# sensores.net
KiCad netlist of a schematic drawn in EAGLE
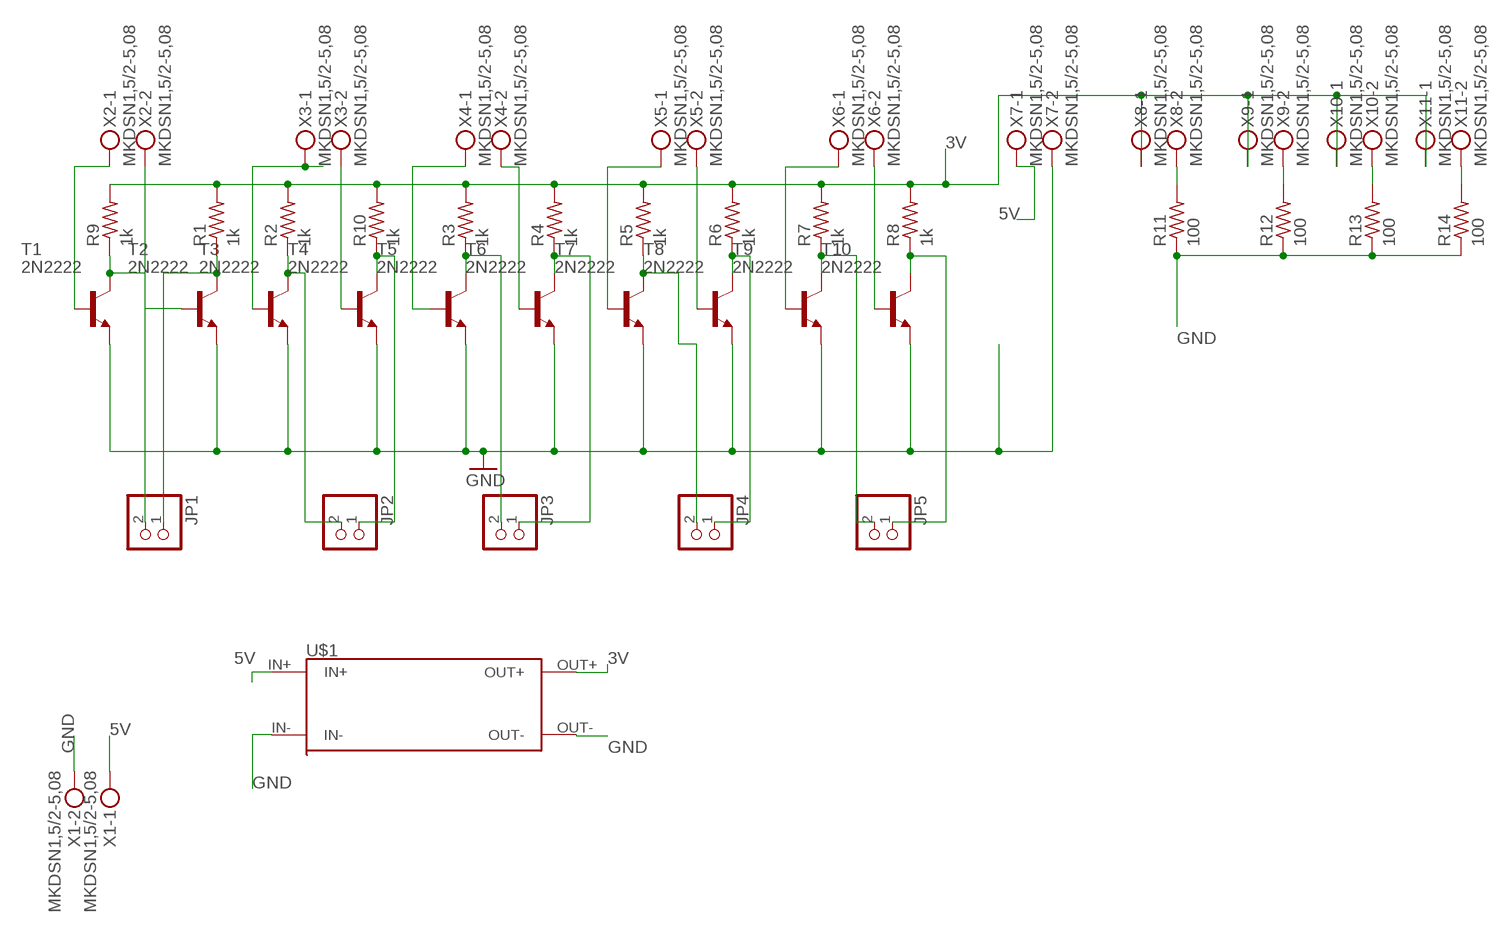
[diagram p0: schematic, sheet 1]

(export (version "E")
  (design (tool "Eeschema 10.0.6"))
  (components
    (comp (ref "JP1")
      (value "PINHD-1X2")
      (footprint "eagle-import:1X02")
      (libsource (lib "eagle-import") (part "PINHD-1X2"))
    )
    (comp (ref "JP2")
      (value "PINHD-1X2")
      (footprint "eagle-import:1X02")
      (libsource (lib "eagle-import") (part "PINHD-1X2"))
    )
    (comp (ref "JP3")
      (value "PINHD-1X2")
      (footprint "eagle-import:1X02")
      (libsource (lib "eagle-import") (part "PINHD-1X2"))
    )
    (comp (ref "JP4")
      (value "PINHD-1X2")
      (footprint "eagle-import:1X02")
      (libsource (lib "eagle-import") (part "PINHD-1X2"))
    )
    (comp (ref "JP5")
      (value "PINHD-1X2")
      (footprint "eagle-import:1X02")
      (libsource (lib "eagle-import") (part "PINHD-1X2"))
    )
    (comp (ref "R1")
      (value "1k")
      (footprint "eagle-import:0207_10")
      (libsource (lib "eagle-import") (part "R-US_0207/10"))
    )
    (comp (ref "R2")
      (value "1k")
      (footprint "eagle-import:0207_10")
      (libsource (lib "eagle-import") (part "R-US_0207/10"))
    )
    (comp (ref "R3")
      (value "1k")
      (footprint "eagle-import:0207_10")
      (libsource (lib "eagle-import") (part "R-US_0207/10"))
    )
    (comp (ref "R4")
      (value "1k")
      (footprint "eagle-import:0207_10")
      (libsource (lib "eagle-import") (part "R-US_0207/10"))
    )
    (comp (ref "R5")
      (value "1k")
      (footprint "eagle-import:0207_10")
      (libsource (lib "eagle-import") (part "R-US_0207/10"))
    )
    (comp (ref "R6")
      (value "1k")
      (footprint "eagle-import:0207_10")
      (libsource (lib "eagle-import") (part "R-US_0207/10"))
    )
    (comp (ref "R7")
      (value "1k")
      (footprint "eagle-import:0207_10")
      (libsource (lib "eagle-import") (part "R-US_0207/10"))
    )
    (comp (ref "R8")
      (value "1k")
      (footprint "eagle-import:0207_10")
      (libsource (lib "eagle-import") (part "R-US_0207/10"))
    )
    (comp (ref "R9")
      (value "1k")
      (footprint "eagle-import:0207_10")
      (libsource (lib "eagle-import") (part "R-US_0207/10"))
    )
    (comp (ref "R10")
      (value "1k")
      (footprint "eagle-import:0207_10")
      (libsource (lib "eagle-import") (part "R-US_0207/10"))
    )
    (comp (ref "R11")
      (value "100")
      (footprint "eagle-import:0207_10")
      (libsource (lib "eagle-import") (part "R-US_0207/10"))
    )
    (comp (ref "R12")
      (value "100")
      (footprint "eagle-import:0207_10")
      (libsource (lib "eagle-import") (part "R-US_0207/10"))
    )
    (comp (ref "R13")
      (value "100")
      (footprint "eagle-import:0207_10")
      (libsource (lib "eagle-import") (part "R-US_0207/10"))
    )
    (comp (ref "R14")
      (value "100")
      (footprint "eagle-import:0207_10")
      (libsource (lib "eagle-import") (part "R-US_0207/10"))
    )
    (comp (ref "T1")
      (value "2N2222")
      (footprint "eagle-import:2N2222")
      (libsource (lib "eagle-import") (part "2N2222"))
    )
    (comp (ref "T2")
      (value "2N2222")
      (footprint "eagle-import:2N2222")
      (libsource (lib "eagle-import") (part "2N2222"))
    )
    (comp (ref "T3")
      (value "2N2222")
      (footprint "eagle-import:2N2222")
      (libsource (lib "eagle-import") (part "2N2222"))
    )
    (comp (ref "T4")
      (value "2N2222")
      (footprint "eagle-import:2N2222")
      (libsource (lib "eagle-import") (part "2N2222"))
    )
    (comp (ref "T5")
      (value "2N2222")
      (footprint "eagle-import:2N2222")
      (libsource (lib "eagle-import") (part "2N2222"))
    )
    (comp (ref "T6")
      (value "2N2222")
      (footprint "eagle-import:2N2222")
      (libsource (lib "eagle-import") (part "2N2222"))
    )
    (comp (ref "T7")
      (value "2N2222")
      (footprint "eagle-import:2N2222")
      (libsource (lib "eagle-import") (part "2N2222"))
    )
    (comp (ref "T8")
      (value "2N2222")
      (footprint "eagle-import:2N2222")
      (libsource (lib "eagle-import") (part "2N2222"))
    )
    (comp (ref "T9")
      (value "2N2222")
      (footprint "eagle-import:2N2222")
      (libsource (lib "eagle-import") (part "2N2222"))
    )
    (comp (ref "T10")
      (value "2N2222")
      (footprint "eagle-import:2N2222")
      (libsource (lib "eagle-import") (part "2N2222"))
    )
    (comp (ref "U$1")
      (value "LM2596")
      (footprint "eagle-import:LM2596")
      (libsource (lib "eagle-import") (part "LM2596"))
    )
    (comp (ref "X1")
      (value "MKDSN1,5/2-5,08")
      (footprint "eagle-import:MKDSN1,5_2-5,08")
      (libsource (lib "eagle-import") (part "MKDSN1,5/2-5,08"))
    )
    (comp (ref "X2")
      (value "MKDSN1,5/2-5,08")
      (footprint "eagle-import:MKDSN1,5_2-5,08")
      (libsource (lib "eagle-import") (part "MKDSN1,5/2-5,08"))
    )
    (comp (ref "X3")
      (value "MKDSN1,5/2-5,08")
      (footprint "eagle-import:MKDSN1,5_2-5,08")
      (libsource (lib "eagle-import") (part "MKDSN1,5/2-5,08"))
    )
    (comp (ref "X4")
      (value "MKDSN1,5/2-5,08")
      (footprint "eagle-import:MKDSN1,5_2-5,08")
      (libsource (lib "eagle-import") (part "MKDSN1,5/2-5,08"))
    )
    (comp (ref "X5")
      (value "MKDSN1,5/2-5,08")
      (footprint "eagle-import:MKDSN1,5_2-5,08")
      (libsource (lib "eagle-import") (part "MKDSN1,5/2-5,08"))
    )
    (comp (ref "X6")
      (value "MKDSN1,5/2-5,08")
      (footprint "eagle-import:MKDSN1,5_2-5,08")
      (libsource (lib "eagle-import") (part "MKDSN1,5/2-5,08"))
    )
    (comp (ref "X7")
      (value "MKDSN1,5/2-5,08")
      (footprint "eagle-import:MKDSN1,5_2-5,08")
      (libsource (lib "eagle-import") (part "MKDSN1,5/2-5,08"))
    )
    (comp (ref "X8")
      (value "MKDSN1,5/2-5,08")
      (footprint "eagle-import:MKDSN1,5_2-5,08")
      (libsource (lib "eagle-import") (part "MKDSN1,5/2-5,08"))
    )
    (comp (ref "X9")
      (value "MKDSN1,5/2-5,08")
      (footprint "eagle-import:MKDSN1,5_2-5,08")
      (libsource (lib "eagle-import") (part "MKDSN1,5/2-5,08"))
    )
    (comp (ref "X10")
      (value "MKDSN1,5/2-5,08")
      (footprint "eagle-import:MKDSN1,5_2-5,08")
      (libsource (lib "eagle-import") (part "MKDSN1,5/2-5,08"))
    )
    (comp (ref "X11")
      (value "MKDSN1,5/2-5,08")
      (footprint "eagle-import:MKDSN1,5_2-5,08")
      (libsource (lib "eagle-import") (part "MKDSN1,5/2-5,08"))
    )
  )
  (nets
    (net (code "1") (name "/3V") (class "Default")
      (node (ref "R1") (pin "2") (pinfunction "2_2") (pintype "passive"))
      (node (ref "R10") (pin "2") (pinfunction "2_2") (pintype "passive"))
      (node (ref "R2") (pin "2") (pinfunction "2_2") (pintype "passive"))
      (node (ref "R3") (pin "2") (pinfunction "2_2") (pintype "passive"))
      (node (ref "R4") (pin "2") (pinfunction "2_2") (pintype "passive"))
      (node (ref "R5") (pin "2") (pinfunction "2_2") (pintype "passive"))
      (node (ref "R6") (pin "2") (pinfunction "2_2") (pintype "passive"))
      (node (ref "R7") (pin "2") (pinfunction "2_2") (pintype "passive"))
      (node (ref "R8") (pin "2") (pinfunction "2_2") (pintype "passive"))
      (node (ref "R9") (pin "2") (pinfunction "2_2") (pintype "passive"))
      (node (ref "U$1") (pin "OUT+") (pinfunction "OUT+_OUT+") (pintype "bidirectional"))
      (node (ref "X10") (pin "1") (pinfunction "KL_1") (pintype "passive"))
      (node (ref "X11") (pin "1") (pinfunction "KL_1") (pintype "passive"))
      (node (ref "X8") (pin "1") (pinfunction "KL_1") (pintype "passive"))
      (node (ref "X9") (pin "1") (pinfunction "KL_1") (pintype "passive"))
    )
    (net (code "2") (name "/5V") (class "Default")
      (node (ref "U$1") (pin "IN+") (pinfunction "IN+_IN+") (pintype "bidirectional"))
      (node (ref "X1") (pin "1") (pinfunction "KL_1") (pintype "passive"))
      (node (ref "X7") (pin "1") (pinfunction "KL_1") (pintype "passive"))
    )
    (net (code "3") (name "GND") (class "Default")
      (node (ref "R11") (pin "1") (pinfunction "1_1") (pintype "passive"))
      (node (ref "R12") (pin "1") (pinfunction "1_1") (pintype "passive"))
      (node (ref "R13") (pin "1") (pinfunction "1_1") (pintype "passive"))
      (node (ref "R14") (pin "1") (pinfunction "1_1") (pintype "passive"))
      (node (ref "T1") (pin "E") (pinfunction "E_E") (pintype "passive"))
      (node (ref "T10") (pin "E") (pinfunction "E_E") (pintype "passive"))
      (node (ref "T2") (pin "E") (pinfunction "E_E") (pintype "passive"))
      (node (ref "T3") (pin "E") (pinfunction "E_E") (pintype "passive"))
      (node (ref "T4") (pin "E") (pinfunction "E_E") (pintype "passive"))
      (node (ref "T5") (pin "E") (pinfunction "E_E") (pintype "passive"))
      (node (ref "T6") (pin "E") (pinfunction "E_E") (pintype "passive"))
      (node (ref "T7") (pin "E") (pinfunction "E_E") (pintype "passive"))
      (node (ref "T8") (pin "E") (pinfunction "E_E") (pintype "passive"))
      (node (ref "T9") (pin "E") (pinfunction "E_E") (pintype "passive"))
      (node (ref "U$1") (pin "IN-") (pinfunction "IN-_IN-") (pintype "bidirectional"))
      (node (ref "U$1") (pin "OUT-") (pinfunction "OUT-_OUT-") (pintype "bidirectional"))
      (node (ref "X1") (pin "2") (pinfunction "KL_2") (pintype "passive"))
      (node (ref "X7") (pin "2") (pinfunction "KL_2") (pintype "passive"))
    )
    (net (code "4") (name "Net-(JP1-Pad1)") (class "Default")
      (node (ref "JP1") (pin "1") (pinfunction "1_1") (pintype "passive"))
      (node (ref "R1") (pin "1") (pinfunction "1_1") (pintype "passive"))
      (node (ref "T2") (pin "C") (pinfunction "C_C") (pintype "passive"))
    )
    (net (code "5") (name "Net-(JP1-Pad2)") (class "Default")
      (node (ref "JP1") (pin "2") (pinfunction "2_2") (pintype "passive"))
      (node (ref "R9") (pin "1") (pinfunction "1_1") (pintype "passive"))
      (node (ref "T1") (pin "C") (pinfunction "C_C") (pintype "passive"))
    )
    (net (code "6") (name "Net-(JP2-Pad1)") (class "Default")
      (node (ref "JP2") (pin "1") (pinfunction "1_1") (pintype "passive"))
      (node (ref "R10") (pin "1") (pinfunction "1_1") (pintype "passive"))
      (node (ref "T4") (pin "C") (pinfunction "C_C") (pintype "passive"))
    )
    (net (code "7") (name "Net-(JP2-Pad2)") (class "Default")
      (node (ref "JP2") (pin "2") (pinfunction "2_2") (pintype "passive"))
      (node (ref "R2") (pin "1") (pinfunction "1_1") (pintype "passive"))
      (node (ref "T3") (pin "C") (pinfunction "C_C") (pintype "passive"))
    )
    (net (code "8") (name "Net-(JP3-Pad1)") (class "Default")
      (node (ref "JP3") (pin "1") (pinfunction "1_1") (pintype "passive"))
      (node (ref "R4") (pin "1") (pinfunction "1_1") (pintype "passive"))
      (node (ref "T6") (pin "C") (pinfunction "C_C") (pintype "passive"))
    )
    (net (code "9") (name "Net-(JP3-Pad2)") (class "Default")
      (node (ref "JP3") (pin "2") (pinfunction "2_2") (pintype "passive"))
      (node (ref "R3") (pin "1") (pinfunction "1_1") (pintype "passive"))
      (node (ref "T5") (pin "C") (pinfunction "C_C") (pintype "passive"))
    )
    (net (code "10") (name "Net-(JP4-Pad1)") (class "Default")
      (node (ref "JP4") (pin "1") (pinfunction "1_1") (pintype "passive"))
      (node (ref "R6") (pin "1") (pinfunction "1_1") (pintype "passive"))
      (node (ref "T8") (pin "C") (pinfunction "C_C") (pintype "passive"))
    )
    (net (code "11") (name "Net-(JP4-Pad2)") (class "Default")
      (node (ref "JP4") (pin "2") (pinfunction "2_2") (pintype "passive"))
      (node (ref "R5") (pin "1") (pinfunction "1_1") (pintype "passive"))
      (node (ref "T7") (pin "C") (pinfunction "C_C") (pintype "passive"))
    )
    (net (code "12") (name "Net-(JP5-Pad1)") (class "Default")
      (node (ref "JP5") (pin "1") (pinfunction "1_1") (pintype "passive"))
      (node (ref "R8") (pin "1") (pinfunction "1_1") (pintype "passive"))
      (node (ref "T10") (pin "C") (pinfunction "C_C") (pintype "passive"))
    )
    (net (code "13") (name "Net-(JP5-Pad2)") (class "Default")
      (node (ref "JP5") (pin "2") (pinfunction "2_2") (pintype "passive"))
      (node (ref "R7") (pin "1") (pinfunction "1_1") (pintype "passive"))
      (node (ref "T9") (pin "C") (pinfunction "C_C") (pintype "passive"))
    )
    (net (code "14") (name "Net-(X2A-KL)") (class "Default")
      (node (ref "T1") (pin "B") (pinfunction "B_B") (pintype "passive"))
      (node (ref "X2") (pin "1") (pinfunction "KL_1") (pintype "passive"))
    )
    (net (code "15") (name "Net-(X2B-KL)") (class "Default")
      (node (ref "T2") (pin "B") (pinfunction "B_B") (pintype "passive"))
      (node (ref "X2") (pin "2") (pinfunction "KL_2") (pintype "passive"))
    )
    (net (code "16") (name "Net-(X3A-KL)") (class "Default")
      (node (ref "T3") (pin "B") (pinfunction "B_B") (pintype "passive"))
      (node (ref "X3") (pin "1") (pinfunction "KL_1") (pintype "passive"))
    )
    (net (code "17") (name "Net-(X3B-KL)") (class "Default")
      (node (ref "T4") (pin "B") (pinfunction "B_B") (pintype "passive"))
      (node (ref "X3") (pin "2") (pinfunction "KL_2") (pintype "passive"))
    )
    (net (code "18") (name "Net-(X4A-KL)") (class "Default")
      (node (ref "T5") (pin "B") (pinfunction "B_B") (pintype "passive"))
      (node (ref "X4") (pin "1") (pinfunction "KL_1") (pintype "passive"))
    )
    (net (code "19") (name "Net-(X4B-KL)") (class "Default")
      (node (ref "T6") (pin "B") (pinfunction "B_B") (pintype "passive"))
      (node (ref "X4") (pin "2") (pinfunction "KL_2") (pintype "passive"))
    )
    (net (code "20") (name "Net-(X5A-KL)") (class "Default")
      (node (ref "T7") (pin "B") (pinfunction "B_B") (pintype "passive"))
      (node (ref "X5") (pin "1") (pinfunction "KL_1") (pintype "passive"))
    )
    (net (code "21") (name "Net-(X5B-KL)") (class "Default")
      (node (ref "T8") (pin "B") (pinfunction "B_B") (pintype "passive"))
      (node (ref "X5") (pin "2") (pinfunction "KL_2") (pintype "passive"))
    )
    (net (code "22") (name "Net-(X6A-KL)") (class "Default")
      (node (ref "T9") (pin "B") (pinfunction "B_B") (pintype "passive"))
      (node (ref "X6") (pin "1") (pinfunction "KL_1") (pintype "passive"))
    )
    (net (code "23") (name "Net-(X6B-KL)") (class "Default")
      (node (ref "T10") (pin "B") (pinfunction "B_B") (pintype "passive"))
      (node (ref "X6") (pin "2") (pinfunction "KL_2") (pintype "passive"))
    )
    (net (code "24") (name "Net-(X8B-KL)") (class "Default")
      (node (ref "R11") (pin "2") (pinfunction "2_2") (pintype "passive"))
      (node (ref "X8") (pin "2") (pinfunction "KL_2") (pintype "passive"))
    )
    (net (code "25") (name "Net-(X9B-KL)") (class "Default")
      (node (ref "R12") (pin "2") (pinfunction "2_2") (pintype "passive"))
      (node (ref "X9") (pin "2") (pinfunction "KL_2") (pintype "passive"))
    )
    (net (code "26") (name "Net-(X10B-KL)") (class "Default")
      (node (ref "R13") (pin "2") (pinfunction "2_2") (pintype "passive"))
      (node (ref "X10") (pin "2") (pinfunction "KL_2") (pintype "passive"))
    )
    (net (code "27") (name "Net-(X11B-KL)") (class "Default")
      (node (ref "R14") (pin "2") (pinfunction "2_2") (pintype "passive"))
      (node (ref "X11") (pin "2") (pinfunction "KL_2") (pintype "passive"))
    )
  )
)
